# Power_Supply_Section.net
KiCad netlist of a schematic drawn in Altium Designer
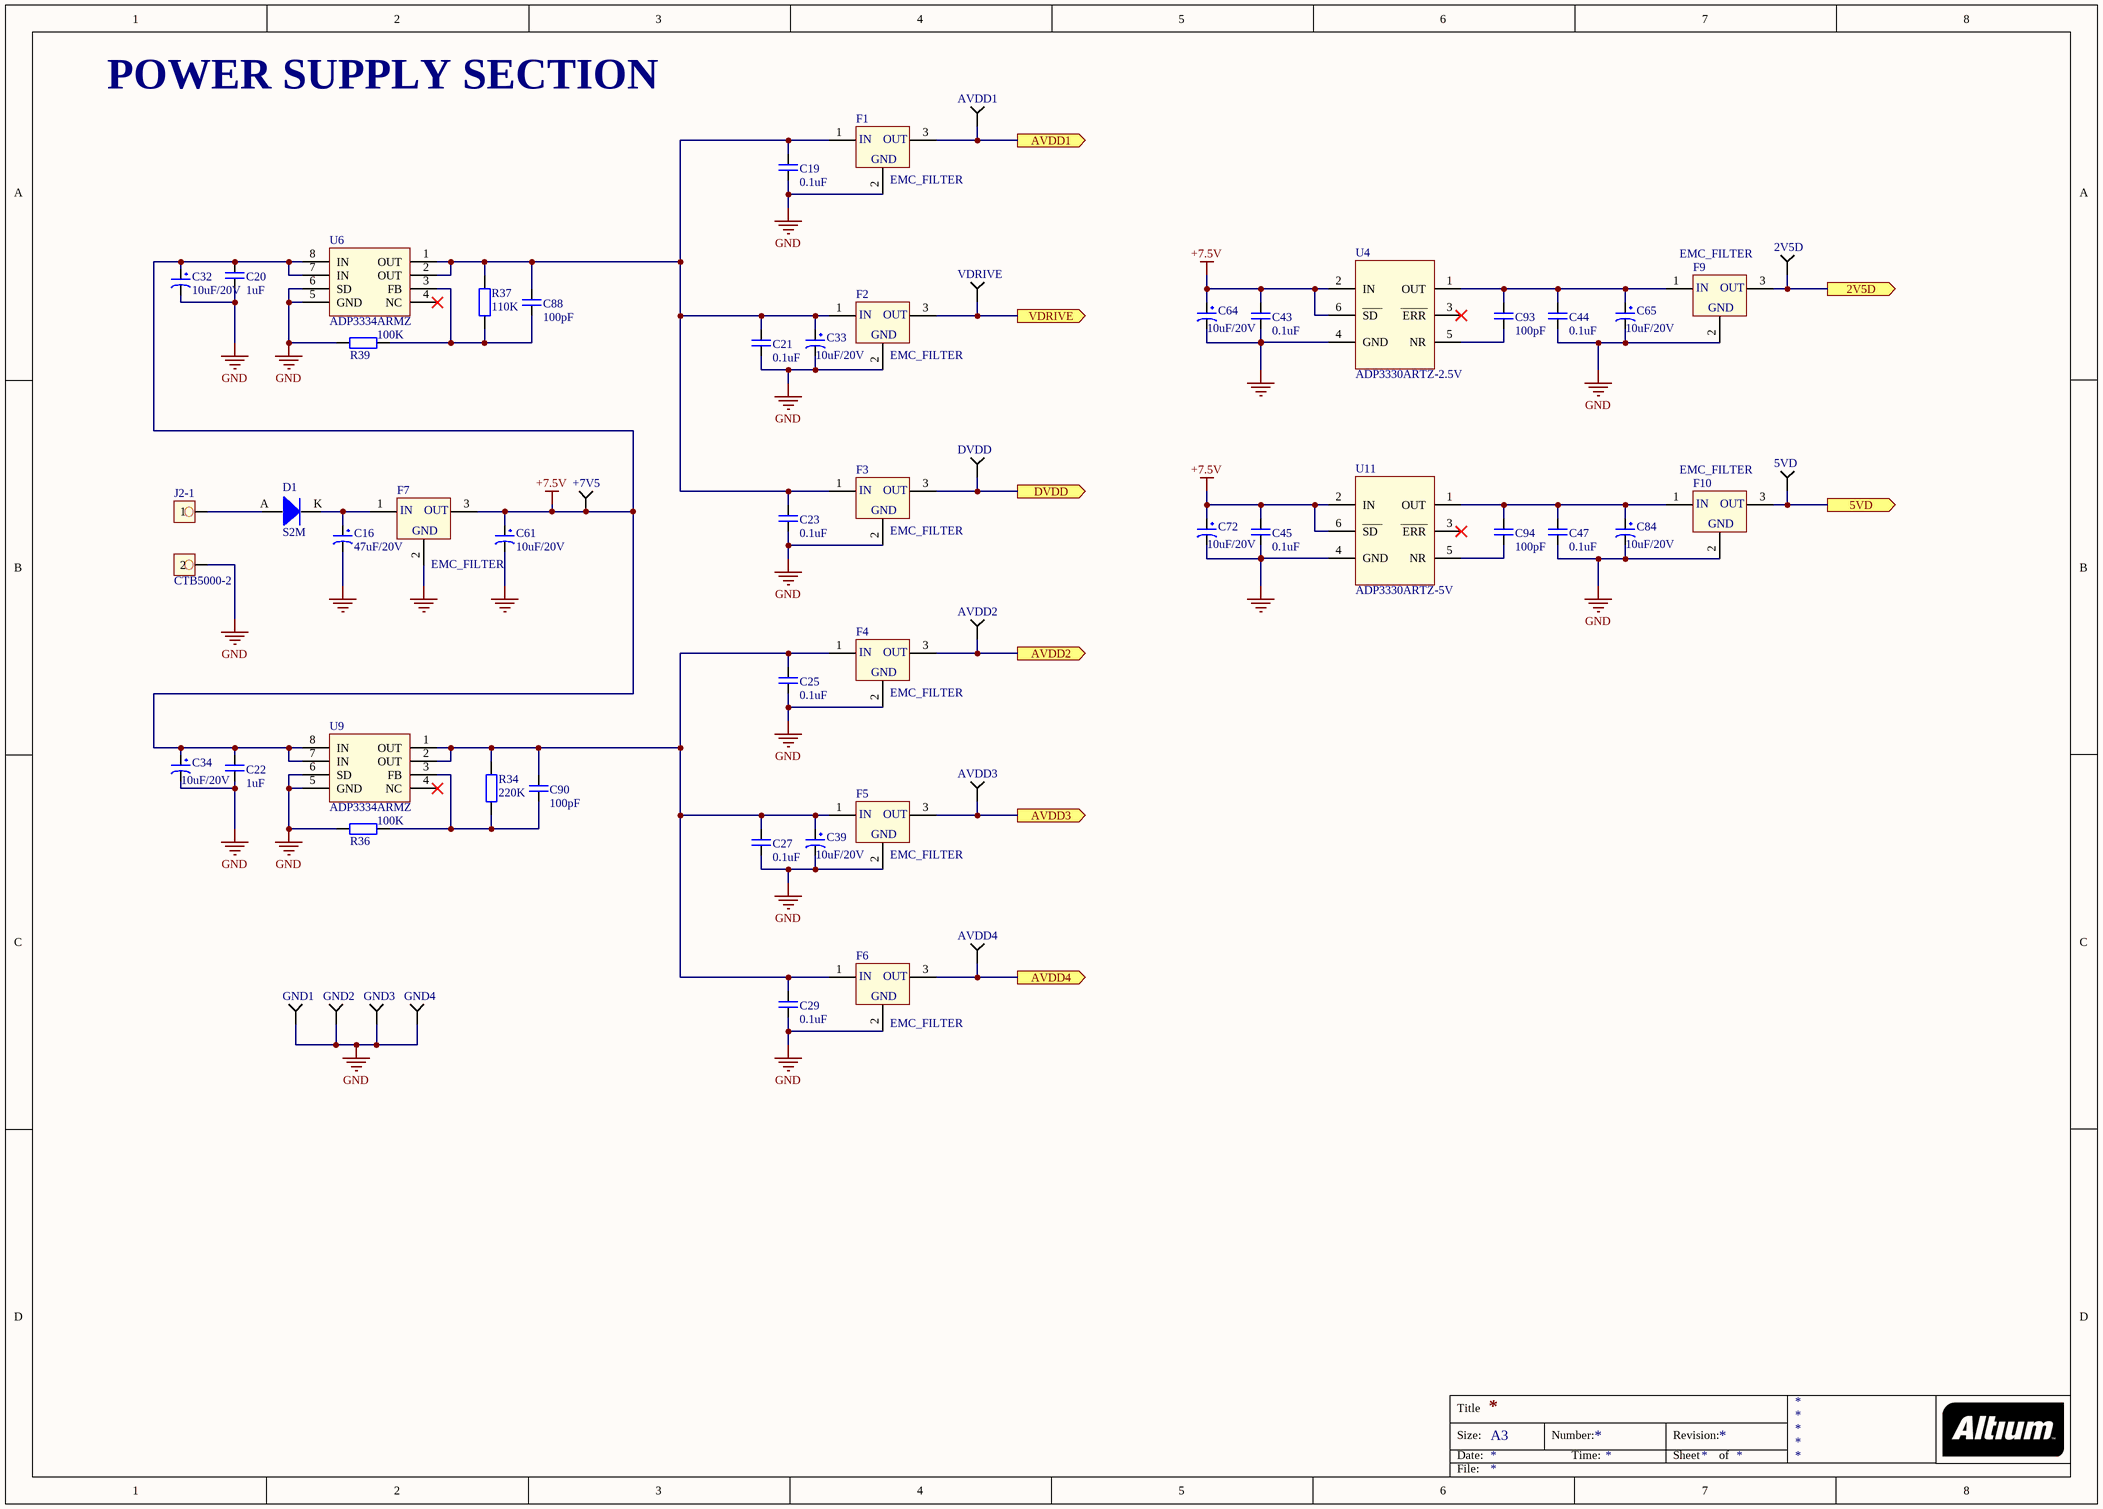
[diagram p0: Power Supply Section.SchDoc]

(export (version "E")
  (design (tool "Eeschema 10.0.6"))
  (components
    (comp (ref "+7V5")
      (value "Test point")
      (footprint "Test Point")
      (description "CONN HEADER VERT .100 1POS 30AU")
      (fields
        (field (name "MANUFACTURER") "TE Connectivity AMP Connectors")
        (field (name "MANUFACTURER PART NUMBER") "87220-1")
      )
      (libsource (lib "AD7763EDZ_Schematics Library") (part "Testpoint_PIN"))
    )
    (comp (ref "2V5D")
      (value "Test point")
      (footprint "Test Point")
      (description "CONN HEADER VERT .100 1POS 30AU")
      (fields
        (field (name "MANUFACTURER") "TE Connectivity AMP Connectors")
        (field (name "MANUFACTURER PART NUMBER") "87220-1")
      )
      (libsource (lib "AD7763EDZ_Schematics Library") (part "Testpoint_PIN"))
    )
    (comp (ref "5VD")
      (value "Test point")
      (footprint "Test Point")
      (description "CONN HEADER VERT .100 1POS 30AU")
      (fields
        (field (name "MANUFACTURER") "TE Connectivity AMP Connectors")
        (field (name "MANUFACTURER PART NUMBER") "87220-1")
      )
      (libsource (lib "AD7763EDZ_Schematics Library") (part "Testpoint_PIN"))
    )
    (comp (ref "AVDD1")
      (value "Test point")
      (footprint "Test Point")
      (description "CONN HEADER VERT .100 1POS 30AU")
      (fields
        (field (name "MANUFACTURER") "TE Connectivity AMP Connectors")
        (field (name "MANUFACTURER PART NUMBER") "87220-1")
      )
      (libsource (lib "AD7763EDZ_Schematics Library") (part "Testpoint_PIN"))
    )
    (comp (ref "AVDD2")
      (value "Test point")
      (footprint "Test Point")
      (description "CONN HEADER VERT .100 1POS 30AU")
      (fields
        (field (name "MANUFACTURER") "TE Connectivity AMP Connectors")
        (field (name "MANUFACTURER PART NUMBER") "87220-1")
      )
      (libsource (lib "AD7763EDZ_Schematics Library") (part "Testpoint_PIN"))
    )
    (comp (ref "AVDD3")
      (value "Test point")
      (footprint "Test Point")
      (description "CONN HEADER VERT .100 1POS 30AU")
      (fields
        (field (name "MANUFACTURER") "TE Connectivity AMP Connectors")
        (field (name "MANUFACTURER PART NUMBER") "87220-1")
      )
      (libsource (lib "AD7763EDZ_Schematics Library") (part "Testpoint_PIN"))
    )
    (comp (ref "AVDD4")
      (value "Test point")
      (footprint "Test Point")
      (description "CONN HEADER VERT .100 1POS 30AU")
      (fields
        (field (name "MANUFACTURER") "TE Connectivity AMP Connectors")
        (field (name "MANUFACTURER PART NUMBER") "87220-1")
      )
      (libsource (lib "AD7763EDZ_Schematics Library") (part "Testpoint_PIN"))
    )
    (comp (ref "C16")
      (value "47uF/20V")
      (footprint "C_TANTA_TAJ-D")
      (description "CAP TANT 47UF 20V 10% 2917_TAJ-D")
      (fields
        (field (name "MANUFACTURER") "AVX Corporation")
        (field (name "MANUFACTURER PART NUMBER") "TAJD476K020RNJ")
      )
      (libsource (lib "AD7763EDZ_Schematics Library") (part "C_TANTA_47uF_20V"))
    )
    (comp (ref "C19")
      (value "0.1uF")
      (footprint "C_0805")
      (description "CAP CER 0.1UF 50V 10% X7R 0805")
      (fields
        (field (name "MANUFACTURER") "MULTICOMP")
        (field (name "MANUFACTURER PART NUMBER") "MCU0805R104KCT")
      )
      (libsource (lib "AD7763EDZ_Schematics Library") (part "C_0.1uF_0805"))
    )
    (comp (ref "C20")
      (value "1uF")
      (footprint "C_0805")
      (description "CAP CER 1UF 16V 10% X7R 0805")
      (fields
        (field (name "MANUFACTURER") "Murata Electronics North America")
        (field (name "MANUFACTURER PART NUMBER") "GRM21BR71C105KA01L")
      )
      (libsource (lib "AD7763EDZ_Schematics Library") (part "C_1uF"))
    )
    (comp (ref "C21")
      (value "0.1uF")
      (footprint "C_0805")
      (description "CAP CER 0.1UF 50V 10% X7R 0805")
      (fields
        (field (name "MANUFACTURER") "MULTICOMP")
        (field (name "MANUFACTURER PART NUMBER") "MCU0805R104KCT")
      )
      (libsource (lib "AD7763EDZ_Schematics Library") (part "C_0.1uF_0805"))
    )
    (comp (ref "C22")
      (value "1uF")
      (footprint "C_0805")
      (description "CAP CER 1UF 16V 10% X7R 0805")
      (fields
        (field (name "MANUFACTURER") "Murata Electronics North America")
        (field (name "MANUFACTURER PART NUMBER") "GRM21BR71C105KA01L")
      )
      (libsource (lib "AD7763EDZ_Schematics Library") (part "C_1uF_0805"))
    )
    (comp (ref "C23")
      (value "0.1uF")
      (footprint "C_0805")
      (description "CAP CER 0.1UF 50V 10% X7R 0805")
      (fields
        (field (name "MANUFACTURER") "MULTICOMP")
        (field (name "MANUFACTURER PART NUMBER") "MCU0805R104KCT")
      )
      (libsource (lib "AD7763EDZ_Schematics Library") (part "C_0.1uF_0805"))
    )
    (comp (ref "C25")
      (value "0.1uF")
      (footprint "C_0805")
      (description "CAP CER 0.1UF 50V 10% X7R 0805")
      (fields
        (field (name "MANUFACTURER") "MULTICOMP")
        (field (name "MANUFACTURER PART NUMBER") "MCU0805R104KCT")
      )
      (libsource (lib "AD7763EDZ_Schematics Library") (part "C_0.1uF_0805"))
    )
    (comp (ref "C27")
      (value "0.1uF")
      (footprint "C_0805")
      (description "CAP CER 0.1UF 50V 10% X7R 0805")
      (fields
        (field (name "MANUFACTURER") "MULTICOMP")
        (field (name "MANUFACTURER PART NUMBER") "MCU0805R104KCT")
      )
      (libsource (lib "AD7763EDZ_Schematics Library") (part "C_0.1uF_0805"))
    )
    (comp (ref "C29")
      (value "0.1uF")
      (footprint "C_0805")
      (description "CAP CER 0.1UF 50V 10% X7R 0805")
      (fields
        (field (name "MANUFACTURER") "MULTICOMP")
        (field (name "MANUFACTURER PART NUMBER") "MCU0805R104KCT")
      )
      (libsource (lib "AD7763EDZ_Schematics Library") (part "C_0.1uF_0805"))
    )
    (comp (ref "C32")
      (value "10uF/20V")
      (footprint "C_TANTA_TAJ-B")
      (description "CAP TANT 10UF 20V 10% 1210")
      (fields
        (field (name "MANUFACTURER") "AVX Corporation")
        (field (name "MANUFACTURER PART NUMBER") "TAJB106K020RNJ")
      )
      (libsource (lib "AD7763EDZ_Schematics Library") (part "C_TANTA_10uF_20V"))
    )
    (comp (ref "C33")
      (value "10uF/20V")
      (footprint "C_TANTA_TAJ-B")
      (description "CAP TANT 10UF 20V 10% 1210")
      (fields
        (field (name "MANUFACTURER") "AVX Corporation")
        (field (name "MANUFACTURER PART NUMBER") "TAJB106K020RNJ")
      )
      (libsource (lib "AD7763EDZ_Schematics Library") (part "C_TANTA_10uF_20V"))
    )
    (comp (ref "C34")
      (value "10uF/20V")
      (footprint "C_TANTA_TAJ-B")
      (description "CAP TANT 10UF 20V 10% 1210")
      (fields
        (field (name "MANUFACTURER") "AVX Corporation")
        (field (name "MANUFACTURER PART NUMBER") "TAJB106K020RNJ")
      )
      (libsource (lib "AD7763EDZ_Schematics Library") (part "C_TANTA_10uF_20V"))
    )
    (comp (ref "C39")
      (value "10uF/20V")
      (footprint "C_TANTA_TAJ-B")
      (description "CAP TANT 10UF 20V 10% 1210")
      (fields
        (field (name "MANUFACTURER") "AVX Corporation")
        (field (name "MANUFACTURER PART NUMBER") "TAJB106K020RNJ")
      )
      (libsource (lib "AD7763EDZ_Schematics Library") (part "C_TANTA_10uF_20V"))
    )
    (comp (ref "C43")
      (value "0.1uF")
      (footprint "C_0805")
      (description "CAP CER 0.1UF 50V 10% X7R 0805")
      (fields
        (field (name "MANUFACTURER") "MULTICOMP")
        (field (name "MANUFACTURER PART NUMBER") "MCU0805R104KCT")
      )
      (libsource (lib "AD7763EDZ_Schematics Library") (part "C_0.1uF_0805"))
    )
    (comp (ref "C44")
      (value "0.1uF")
      (footprint "C_0805")
      (description "CAP CER 0.1UF 50V 10% X7R 0805")
      (fields
        (field (name "MANUFACTURER") "MULTICOMP")
        (field (name "MANUFACTURER PART NUMBER") "MCU0805R104KCT")
      )
      (libsource (lib "AD7763EDZ_Schematics Library") (part "C_0.1uF_0805"))
    )
    (comp (ref "C45")
      (value "0.1uF")
      (footprint "C_0805")
      (description "CAP CER 0.1UF 50V 10% X7R 0805")
      (fields
        (field (name "MANUFACTURER") "MULTICOMP")
        (field (name "MANUFACTURER PART NUMBER") "MCU0805R104KCT")
      )
      (libsource (lib "AD7763EDZ_Schematics Library") (part "C_0.1uF_0805"))
    )
    (comp (ref "C47")
      (value "0.1uF")
      (footprint "C_0805")
      (description "CAP CER 0.1UF 50V 10% X7R 0805")
      (fields
        (field (name "MANUFACTURER") "MULTICOMP")
        (field (name "MANUFACTURER PART NUMBER") "MCU0805R104KCT")
      )
      (libsource (lib "AD7763EDZ_Schematics Library") (part "C_0.1uF_0805"))
    )
    (comp (ref "C61")
      (value "10uF/20V")
      (footprint "C_TANTA_TAJ-B")
      (description "CAP TANT 10UF 20V 10% 1210")
      (fields
        (field (name "MANUFACTURER") "AVX Corporation")
        (field (name "MANUFACTURER PART NUMBER") "TAJB106K020RNJ")
      )
      (libsource (lib "AD7763EDZ_Schematics Library") (part "C_TANTA_10uF_20V"))
    )
    (comp (ref "C64")
      (value "10uF/20V")
      (footprint "C_TANTA_TAJ-B")
      (description "CAP TANT 10UF 20V 10% 1210")
      (fields
        (field (name "MANUFACTURER") "AVX Corporation")
        (field (name "MANUFACTURER PART NUMBER") "TAJB106K020RNJ")
      )
      (libsource (lib "AD7763EDZ_Schematics Library") (part "C_TANTA_10uF_20V"))
    )
    (comp (ref "C65")
      (value "10uF/20V")
      (footprint "C_TANTA_TAJ-B")
      (description "CAP TANT 10UF 20V 10% 1210")
      (fields
        (field (name "MANUFACTURER") "AVX Corporation")
        (field (name "MANUFACTURER PART NUMBER") "TAJB106K020RNJ")
      )
      (libsource (lib "AD7763EDZ_Schematics Library") (part "C_TANTA_10uF_20V"))
    )
    (comp (ref "C72")
      (value "10uF/20V")
      (footprint "C_TANTA_TAJ-B")
      (description "CAP TANT 10UF 20V 10% 1210")
      (fields
        (field (name "MANUFACTURER") "AVX Corporation")
        (field (name "MANUFACTURER PART NUMBER") "TAJB106K020RNJ")
      )
      (libsource (lib "AD7763EDZ_Schematics Library") (part "C_TANTA_10uF_20V"))
    )
    (comp (ref "C84")
      (value "10uF/20V")
      (footprint "C_TANTA_TAJ-B")
      (description "CAP TANT 10UF 20V 10% 1210")
      (fields
        (field (name "MANUFACTURER") "AVX Corporation")
        (field (name "MANUFACTURER PART NUMBER") "TAJB106K020RNJ")
      )
      (libsource (lib "AD7763EDZ_Schematics Library") (part "C_TANTA_10uF_20V"))
    )
    (comp (ref "C88")
      (value "100pF")
      (footprint "C0603")
      (description "CAP CER 100PF 50V 5% NP0 0603")
      (fields
        (field (name "MANUFACTURER") "MULTICOMP")
        (field (name "MANUFACTURER PART NUMBER") "MCU0603C101JCT")
      )
      (libsource (lib "AD7763EDZ_Schematics Library") (part "C_100pF_0603"))
    )
    (comp (ref "C90")
      (value "100pF")
      (footprint "C0603")
      (description "CAP CER 100PF 50V 5% NP0 0603")
      (fields
        (field (name "MANUFACTURER") "MULTICOMP")
        (field (name "MANUFACTURER PART NUMBER") "MCU0603C101JCT")
      )
      (libsource (lib "AD7763EDZ_Schematics Library") (part "C_100pF_0603"))
    )
    (comp (ref "C93")
      (value "100pF")
      (footprint "C0603")
      (description "CAP CER 100PF 50V 5% NP0 0603")
      (fields
        (field (name "MANUFACTURER") "MULTICOMP")
        (field (name "MANUFACTURER PART NUMBER") "MCU0603C101JCT")
      )
      (libsource (lib "AD7763EDZ_Schematics Library") (part "C_100pF_0603"))
    )
    (comp (ref "C94")
      (value "100pF")
      (footprint "C0603")
      (description "CAP CER 100PF 50V 5% NP0 0603")
      (fields
        (field (name "MANUFACTURER") "MULTICOMP")
        (field (name "MANUFACTURER PART NUMBER") "MCU0603C101JCT")
      )
      (libsource (lib "AD7763EDZ_Schematics Library") (part "C_100pF_0603"))
    )
    (comp (ref "D1")
      (value "S2M")
      (footprint "SS14_AK")
      (description "DIODE GEN PURP 1KV 2A DO214AA")
      (fields (field (name "MANUFACTURER") "Fairchild Semiconductor"))
      (libsource (lib "AD7763EDZ_Schematics Library") (part "D_S2M"))
    )
    (comp (ref "DVDD")
      (value "Test point")
      (footprint "Test Point")
      (description "CONN HEADER VERT .100 1POS 30AU")
      (fields
        (field (name "MANUFACTURER") "TE Connectivity AMP Connectors")
        (field (name "MANUFACTURER PART NUMBER") "87220-1")
      )
      (libsource (lib "AD7763EDZ_Schematics Library") (part "Testpoint_PIN"))
    )
    (comp (ref "F1")
      (value "EMC_FILTER")
      (footprint "EMC_FILTER")
      (description "FILTER LC HIGH FREQ 1000PF 2606")
      (fields
        (field (name "MANUFACTURER") "Murata Electronics North America")
        (field (name "MANUFACTURER PART NUMBER") "NFE61PT102E1H9L")
      )
      (libsource (lib "AD7763EDZ_Schematics Library") (part "EMC_FILTER"))
    )
    (comp (ref "F2")
      (value "EMC_FILTER")
      (footprint "EMC_FILTER")
      (description "FILTER LC HIGH FREQ 1000PF 2606")
      (fields
        (field (name "MANUFACTURER") "Murata Electronics North America")
        (field (name "MANUFACTURER PART NUMBER") "NFE61PT102E1H9L")
      )
      (libsource (lib "AD7763EDZ_Schematics Library") (part "EMC_FILTER"))
    )
    (comp (ref "F3")
      (value "EMC_FILTER")
      (footprint "EMC_FILTER")
      (description "FILTER LC HIGH FREQ 1000PF 2606")
      (fields
        (field (name "MANUFACTURER") "Murata Electronics North America")
        (field (name "MANUFACTURER PART NUMBER") "NFE61PT102E1H9L")
      )
      (libsource (lib "AD7763EDZ_Schematics Library") (part "EMC_FILTER"))
    )
    (comp (ref "F4")
      (value "EMC_FILTER")
      (footprint "EMC_FILTER")
      (description "FILTER LC HIGH FREQ 1000PF 2606")
      (fields
        (field (name "MANUFACTURER") "Murata Electronics North America")
        (field (name "MANUFACTURER PART NUMBER") "NFE61PT102E1H9L")
      )
      (libsource (lib "AD7763EDZ_Schematics Library") (part "EMC_FILTER"))
    )
    (comp (ref "F5")
      (value "EMC_FILTER")
      (footprint "EMC_FILTER")
      (description "FILTER LC HIGH FREQ 1000PF 2606")
      (fields
        (field (name "MANUFACTURER") "Murata Electronics North America")
        (field (name "MANUFACTURER PART NUMBER") "NFE61PT102E1H9L")
      )
      (libsource (lib "AD7763EDZ_Schematics Library") (part "EMC_FILTER"))
    )
    (comp (ref "F6")
      (value "EMC_FILTER")
      (footprint "EMC_FILTER")
      (description "FILTER LC HIGH FREQ 1000PF 2606")
      (fields
        (field (name "MANUFACTURER") "Murata Electronics North America")
        (field (name "MANUFACTURER PART NUMBER") "NFE61PT102E1H9L")
      )
      (libsource (lib "AD7763EDZ_Schematics Library") (part "EMC_FILTER"))
    )
    (comp (ref "F7")
      (value "EMC_FILTER")
      (footprint "EMC_FILTER")
      (description "FILTER LC HIGH FREQ 1000PF 2606")
      (fields
        (field (name "MANUFACTURER") "Murata Electronics North America")
        (field (name "MANUFACTURER PART NUMBER") "NFE61PT102E1H9L")
      )
      (libsource (lib "AD7763EDZ_Schematics Library") (part "EMC_FILTER"))
    )
    (comp (ref "F9")
      (value "EMC_FILTER")
      (footprint "EMC_FILTER")
      (description "FILTER LC HIGH FREQ 1000PF 2606")
      (fields
        (field (name "MANUFACTURER") "Murata Electronics North America")
        (field (name "MANUFACTURER PART NUMBER") "NFE61PT102E1H9L")
      )
      (libsource (lib "AD7763EDZ_Schematics Library") (part "EMC_FILTER"))
    )
    (comp (ref "F10")
      (value "EMC_FILTER")
      (footprint "EMC_FILTER")
      (description "FILTER LC HIGH FREQ 1000PF 2606")
      (fields
        (field (name "MANUFACTURER") "Murata Electronics North America")
        (field (name "MANUFACTURER PART NUMBER") "NFE61PT102E1H9L")
      )
      (libsource (lib "AD7763EDZ_Schematics Library") (part "EMC_FILTER"))
    )
    (comp (ref "GND1")
      (value "Test point")
      (footprint "Test Point")
      (description "CONN HEADER VERT .100 1POS 30AU")
      (fields
        (field (name "MANUFACTURER") "TE Connectivity AMP Connectors")
        (field (name "MANUFACTURER PART NUMBER") "87220-1")
      )
      (libsource (lib "AD7763EDZ_Schematics Library") (part "Testpoint_PIN"))
    )
    (comp (ref "GND2")
      (value "Test point")
      (footprint "Test Point")
      (description "CONN HEADER VERT .100 1POS 30AU")
      (fields
        (field (name "MANUFACTURER") "TE Connectivity AMP Connectors")
        (field (name "MANUFACTURER PART NUMBER") "87220-1")
      )
      (libsource (lib "AD7763EDZ_Schematics Library") (part "Testpoint_PIN"))
    )
    (comp (ref "GND3")
      (value "Test point")
      (footprint "Test Point")
      (description "CONN HEADER VERT .100 1POS 30AU")
      (fields
        (field (name "MANUFACTURER") "TE Connectivity AMP Connectors")
        (field (name "MANUFACTURER PART NUMBER") "87220-1")
      )
      (libsource (lib "AD7763EDZ_Schematics Library") (part "Testpoint_PIN"))
    )
    (comp (ref "GND4")
      (value "Test point")
      (footprint "Test Point")
      (description "CONN HEADER VERT .100 1POS 30AU")
      (fields
        (field (name "MANUFACTURER") "TE Connectivity AMP Connectors")
        (field (name "MANUFACTURER PART NUMBER") "87220-1")
      )
      (libsource (lib "AD7763EDZ_Schematics Library") (part "Testpoint_PIN"))
    )
    (comp (ref "J2-1")
      (value "CTB5000-2")
      (footprint "CTB5000-2")
      (description "TERMINAL BLOCK, WIRE TO BRD, 2POS, 14AWG")
      (fields
        (field (name "MANUFACTURER") "CAMDENBOSS")
        (field (name "MANUFACTURER PART NUMBER") "CTB5000/2")
      )
      (libsource (lib "AD7763EDZ_Schematics Library") (part "HEADER_2"))
    )
    (comp (ref "R34")
      (value "220K")
      (footprint "R_0603")
      (description "RES SMD 220K OHM 1% 1/16W 0603")
      (fields
        (field (name "MANUFACTURER") "MULTICOMP")
        (field (name "MANUFACTURER PART NUMBER") "MC0063W06031220K")
      )
      (libsource (lib "AD7763EDZ_Schematics Library") (part "R_0603_220K"))
    )
    (comp (ref "R36")
      (value "100K")
      (footprint "R_0603")
      (description "RES SMD 100K OHM 1% 1/16W 0603")
      (fields
        (field (name "MANUFACTURER") "MULTICOMP")
        (field (name "MANUFACTURER PART NUMBER") "MC0063W06031100K")
      )
      (libsource (lib "AD7763EDZ_Schematics Library") (part "R_0603_100K"))
    )
    (comp (ref "R37")
      (value "110K")
      (footprint "R_0603")
      (description "RES SMD 110K OHM 1% 1/16W 0603")
      (fields
        (field (name "MANUFACTURER") "MULTICOMP")
        (field (name "MANUFACTURER PART NUMBER") "MC0063W06031110K")
      )
      (libsource (lib "AD7763EDZ_Schematics Library") (part "R_0603_110K"))
    )
    (comp (ref "R39")
      (value "100K")
      (footprint "R_0603")
      (description "RES SMD 100K OHM 1% 1/16W 0603")
      (fields
        (field (name "MANUFACTURER") "MULTICOMP")
        (field (name "MANUFACTURER PART NUMBER") "MC0063W06031100K")
      )
      (libsource (lib "AD7763EDZ_Schematics Library") (part "R_0603_100K"))
    )
    (comp (ref "U4")
      (value "ADP3330ARTZ-2.5V")
      (footprint "SOT-23-6")
      (description "IC REG LDO 2.5V 0.2A SOT23-6")
      (fields
        (field (name "MANUFACTURER") "Analog Devices Inc.")
        (field (name "MANUFACTURER PART NUMBER") "ADP3330ARTZ-2.5-R7")
      )
      (libsource (lib "AD7763EDZ_Schematics Library") (part "ADP3330ARTZ-2.5V"))
    )
    (comp (ref "U6")
      (value "ADP3334ARMZ")
      (footprint "MSOP-8")
      (description "IC REG LDO ADJ 0.5A 8MSOP")
      (fields
        (field (name "MANUFACTURER") "Analog Devices Inc")
        (field (name "MANUFACTURER PART NUMBER") "ADP3334ARMZ-REEL")
      )
      (libsource (lib "AD7763EDZ_Schematics Library") (part "ADP3334ARMZ"))
    )
    (comp (ref "U9")
      (value "ADP3334ARMZ")
      (footprint "MSOP-8")
      (description "IC REG LDO ADJ 0.5A 8MSOP")
      (fields
        (field (name "MANUFACTURER") "Analog Devices Inc")
        (field (name "MANUFACTURER PART NUMBER") "ADP3334ARMZ-REEL")
      )
      (libsource (lib "AD7763EDZ_Schematics Library") (part "ADP3334ARMZ"))
    )
    (comp (ref "U11")
      (value "ADP3330ARTZ-5V")
      (footprint "SOT-23-6")
      (description "IC REG LDO 5V 0.2A SOT23-6")
      (fields
        (field (name "MANUFACTURER") "Analog Devices Inc.")
        (field (name "MANUFACTURER PART NUMBER") "ADP3330ARTZ-5-RL7")
      )
      (libsource (lib "AD7763EDZ_Schematics Library") (part "ADP3330ARTZ-5V"))
    )
    (comp (ref "VDRIVE")
      (value "Test point")
      (footprint "Test Point")
      (description "CONN HEADER VERT .100 1POS 30AU")
      (fields
        (field (name "MANUFACTURER") "TE Connectivity AMP Connectors")
        (field (name "MANUFACTURER PART NUMBER") "87220-1")
      )
      (libsource (lib "AD7763EDZ_Schematics Library") (part "Testpoint_PIN"))
    )
  )
  (nets
    (net (code "1") (name "+7.5V") (class "Default")
      (node (ref "+7V5") (pin "1") (pinfunction "1_1") (pintype "passive"))
      (node (ref "C20") (pin "1") (pinfunction "1_1") (pintype "passive"))
      (node (ref "C22") (pin "1") (pinfunction "1_1") (pintype "passive"))
      (node (ref "C32") (pin "1") (pinfunction "1_1") (pintype "passive"))
      (node (ref "C34") (pin "1") (pinfunction "1_1") (pintype "passive"))
      (node (ref "C43") (pin "1") (pinfunction "1_1") (pintype "passive"))
      (node (ref "C45") (pin "1") (pinfunction "1_1") (pintype "passive"))
      (node (ref "C61") (pin "1") (pinfunction "1_1") (pintype "passive"))
      (node (ref "C64") (pin "1") (pinfunction "1_1") (pintype "passive"))
      (node (ref "C72") (pin "1") (pinfunction "1_1") (pintype "passive"))
      (node (ref "F7") (pin "3") (pinfunction "OUT_3") (pintype "passive"))
      (node (ref "U11") (pin "2") (pinfunction "IN_2") (pintype "passive"))
      (node (ref "U11") (pin "6") (pinfunction "SD_6") (pintype "passive"))
      (node (ref "U4") (pin "2") (pinfunction "IN_2") (pintype "passive"))
      (node (ref "U4") (pin "6") (pinfunction "SD_6") (pintype "passive"))
      (node (ref "U6") (pin "7") (pinfunction "IN_7") (pintype "passive"))
      (node (ref "U6") (pin "8") (pinfunction "IN_8") (pintype "passive"))
      (node (ref "U9") (pin "7") (pinfunction "IN_7") (pintype "passive"))
      (node (ref "U9") (pin "8") (pinfunction "IN_8") (pintype "passive"))
    )
    (net (code "2") (name "/2V5D") (class "Default")
      (node (ref "2V5D") (pin "1") (pinfunction "1_1") (pintype "passive"))
      (node (ref "F9") (pin "3") (pinfunction "OUT_3") (pintype "passive"))
    )
    (net (code "3") (name "/5VD") (class "Default")
      (node (ref "5VD") (pin "1") (pinfunction "1_1") (pintype "passive"))
      (node (ref "F10") (pin "3") (pinfunction "OUT_3") (pintype "passive"))
    )
    (net (code "4") (name "/AVDD1") (class "Default")
      (node (ref "AVDD1") (pin "1") (pinfunction "1_1") (pintype "passive"))
      (node (ref "F1") (pin "3") (pinfunction "OUT_3") (pintype "passive"))
    )
    (net (code "5") (name "/AVDD2") (class "Default")
      (node (ref "AVDD2") (pin "1") (pinfunction "1_1") (pintype "passive"))
      (node (ref "F4") (pin "3") (pinfunction "OUT_3") (pintype "passive"))
    )
    (net (code "6") (name "/AVDD3") (class "Default")
      (node (ref "AVDD3") (pin "1") (pinfunction "1_1") (pintype "passive"))
      (node (ref "F5") (pin "3") (pinfunction "OUT_3") (pintype "passive"))
    )
    (net (code "7") (name "/AVDD4") (class "Default")
      (node (ref "AVDD4") (pin "1") (pinfunction "1_1") (pintype "passive"))
      (node (ref "F6") (pin "3") (pinfunction "OUT_3") (pintype "passive"))
    )
    (net (code "8") (name "/DVDD") (class "Default")
      (node (ref "DVDD") (pin "1") (pinfunction "1_1") (pintype "passive"))
      (node (ref "F3") (pin "3") (pinfunction "OUT_3") (pintype "passive"))
    )
    (net (code "9") (name "/VDRIVE") (class "Default")
      (node (ref "F2") (pin "3") (pinfunction "OUT_3") (pintype "passive"))
      (node (ref "VDRIVE") (pin "1") (pinfunction "1_1") (pintype "passive"))
    )
    (net (code "10") (name "<NO NET>") (class "Default")
      (node (ref "C16") (pin "2") (pinfunction "2_2") (pintype "passive"))
      (node (ref "C43") (pin "2") (pinfunction "2_2") (pintype "passive"))
      (node (ref "C45") (pin "2") (pinfunction "2_2") (pintype "passive"))
      (node (ref "C61") (pin "2") (pinfunction "2_2") (pintype "passive"))
      (node (ref "C64") (pin "2") (pinfunction "2_2") (pintype "passive"))
      (node (ref "C72") (pin "2") (pinfunction "2_2") (pintype "passive"))
      (node (ref "F7") (pin "2") (pinfunction "GND_2") (pintype "passive"))
      (node (ref "U11") (pin "4") (pinfunction "GND_4") (pintype "passive"))
      (node (ref "U4") (pin "4") (pinfunction "GND_4") (pintype "passive"))
    )
    (net (code "11") (name "GND") (class "Default")
      (node (ref "C19") (pin "2") (pinfunction "2_2") (pintype "passive"))
      (node (ref "C20") (pin "2") (pinfunction "2_2") (pintype "passive"))
      (node (ref "C21") (pin "2") (pinfunction "2_2") (pintype "passive"))
      (node (ref "C22") (pin "2") (pinfunction "2_2") (pintype "passive"))
      (node (ref "C23") (pin "2") (pinfunction "2_2") (pintype "passive"))
      (node (ref "C25") (pin "2") (pinfunction "2_2") (pintype "passive"))
      (node (ref "C27") (pin "2") (pinfunction "2_2") (pintype "passive"))
      (node (ref "C29") (pin "2") (pinfunction "2_2") (pintype "passive"))
      (node (ref "C32") (pin "2") (pinfunction "2_2") (pintype "passive"))
      (node (ref "C33") (pin "2") (pinfunction "2_2") (pintype "passive"))
      (node (ref "C34") (pin "2") (pinfunction "2_2") (pintype "passive"))
      (node (ref "C39") (pin "2") (pinfunction "2_2") (pintype "passive"))
      (node (ref "C44") (pin "2") (pinfunction "2_2") (pintype "passive"))
      (node (ref "C47") (pin "2") (pinfunction "2_2") (pintype "passive"))
      (node (ref "C65") (pin "2") (pinfunction "2_2") (pintype "passive"))
      (node (ref "C84") (pin "2") (pinfunction "2_2") (pintype "passive"))
      (node (ref "F1") (pin "2") (pinfunction "GND_2") (pintype "passive"))
      (node (ref "F10") (pin "2") (pinfunction "GND_2") (pintype "passive"))
      (node (ref "F2") (pin "2") (pinfunction "GND_2") (pintype "passive"))
      (node (ref "F3") (pin "2") (pinfunction "GND_2") (pintype "passive"))
      (node (ref "F4") (pin "2") (pinfunction "GND_2") (pintype "passive"))
      (node (ref "F5") (pin "2") (pinfunction "GND_2") (pintype "passive"))
      (node (ref "F6") (pin "2") (pinfunction "GND_2") (pintype "passive"))
      (node (ref "F9") (pin "2") (pinfunction "GND_2") (pintype "passive"))
      (node (ref "GND1") (pin "1") (pinfunction "1_1") (pintype "passive"))
      (node (ref "GND2") (pin "1") (pinfunction "1_1") (pintype "passive"))
      (node (ref "GND3") (pin "1") (pinfunction "1_1") (pintype "passive"))
      (node (ref "GND4") (pin "1") (pinfunction "1_1") (pintype "passive"))
      (node (ref "J2-1") (pin "2") (pinfunction "2_2") (pintype "passive"))
      (node (ref "R36") (pin "1") (pinfunction "1_1") (pintype "passive"))
      (node (ref "R39") (pin "1") (pinfunction "1_1") (pintype "passive"))
      (node (ref "U6") (pin "5") (pinfunction "GND_5") (pintype "passive"))
      (node (ref "U6") (pin "6") (pinfunction "SD_6") (pintype "passive"))
      (node (ref "U9") (pin "5") (pinfunction "GND_5") (pintype "passive"))
      (node (ref "U9") (pin "6") (pinfunction "SD_6") (pintype "passive"))
    )
    (net (code "12") (name "Net-(D1-PadA)") (class "Default")
      (node (ref "D1") (pin "A") (pinfunction "A_A") (pintype "passive"))
      (node (ref "J2-1") (pin "1") (pinfunction "1_1") (pintype "passive"))
    )
    (net (code "13") (name "Net-(F1-IN)") (class "Default")
      (node (ref "C19") (pin "1") (pinfunction "1_1") (pintype "passive"))
      (node (ref "C21") (pin "1") (pinfunction "1_1") (pintype "passive"))
      (node (ref "C23") (pin "1") (pinfunction "1_1") (pintype "passive"))
      (node (ref "C33") (pin "1") (pinfunction "1_1") (pintype "passive"))
      (node (ref "C88") (pin "1") (pinfunction "1_1") (pintype "passive"))
      (node (ref "F1") (pin "1") (pinfunction "IN_1") (pintype "passive"))
      (node (ref "F2") (pin "1") (pinfunction "IN_1") (pintype "passive"))
      (node (ref "F3") (pin "1") (pinfunction "IN_1") (pintype "passive"))
      (node (ref "R37") (pin "2") (pinfunction "2_2") (pintype "passive"))
      (node (ref "U6") (pin "1") (pinfunction "OUT_1") (pintype "passive"))
      (node (ref "U6") (pin "2") (pinfunction "OUT_2") (pintype "passive"))
    )
    (net (code "14") (name "Net-(F4-IN)") (class "Default")
      (node (ref "C25") (pin "1") (pinfunction "1_1") (pintype "passive"))
      (node (ref "C27") (pin "1") (pinfunction "1_1") (pintype "passive"))
      (node (ref "C29") (pin "1") (pinfunction "1_1") (pintype "passive"))
      (node (ref "C39") (pin "1") (pinfunction "1_1") (pintype "passive"))
      (node (ref "C90") (pin "1") (pinfunction "1_1") (pintype "passive"))
      (node (ref "F4") (pin "1") (pinfunction "IN_1") (pintype "passive"))
      (node (ref "F5") (pin "1") (pinfunction "IN_1") (pintype "passive"))
      (node (ref "F6") (pin "1") (pinfunction "IN_1") (pintype "passive"))
      (node (ref "R34") (pin "2") (pinfunction "2_2") (pintype "passive"))
      (node (ref "U9") (pin "1") (pinfunction "OUT_1") (pintype "passive"))
      (node (ref "U9") (pin "2") (pinfunction "OUT_2") (pintype "passive"))
    )
    (net (code "15") (name "Net-(F7-IN)") (class "Default")
      (node (ref "C16") (pin "1") (pinfunction "1_1") (pintype "passive"))
      (node (ref "D1") (pin "K") (pinfunction "K_K") (pintype "passive"))
      (node (ref "F7") (pin "1") (pinfunction "IN_1") (pintype "passive"))
    )
    (net (code "16") (name "Net-(F9-IN)") (class "Default")
      (node (ref "C44") (pin "1") (pinfunction "1_1") (pintype "passive"))
      (node (ref "C65") (pin "1") (pinfunction "1_1") (pintype "passive"))
      (node (ref "C93") (pin "1") (pinfunction "1_1") (pintype "passive"))
      (node (ref "F9") (pin "1") (pinfunction "IN_1") (pintype "passive"))
      (node (ref "U4") (pin "1") (pinfunction "OUT_1") (pintype "passive"))
    )
    (net (code "17") (name "Net-(F10-IN)") (class "Default")
      (node (ref "C47") (pin "1") (pinfunction "1_1") (pintype "passive"))
      (node (ref "C84") (pin "1") (pinfunction "1_1") (pintype "passive"))
      (node (ref "C94") (pin "1") (pinfunction "1_1") (pintype "passive"))
      (node (ref "F10") (pin "1") (pinfunction "IN_1") (pintype "passive"))
      (node (ref "U11") (pin "1") (pinfunction "OUT_1") (pintype "passive"))
    )
    (net (code "18") (name "Net-(U4-NR)") (class "Default")
      (node (ref "C93") (pin "2") (pinfunction "2_2") (pintype "passive"))
      (node (ref "U4") (pin "5") (pinfunction "NR_5") (pintype "passive"))
    )
    (net (code "19") (name "Net-(U6-FB)") (class "Default")
      (node (ref "C88") (pin "2") (pinfunction "2_2") (pintype "passive"))
      (node (ref "R37") (pin "1") (pinfunction "1_1") (pintype "passive"))
      (node (ref "R39") (pin "2") (pinfunction "2_2") (pintype "passive"))
      (node (ref "U6") (pin "3") (pinfunction "FB_3") (pintype "passive"))
    )
    (net (code "20") (name "Net-(U9-FB)") (class "Default")
      (node (ref "C90") (pin "2") (pinfunction "2_2") (pintype "passive"))
      (node (ref "R34") (pin "1") (pinfunction "1_1") (pintype "passive"))
      (node (ref "R36") (pin "2") (pinfunction "2_2") (pintype "passive"))
      (node (ref "U9") (pin "3") (pinfunction "FB_3") (pintype "passive"))
    )
    (net (code "21") (name "Net-(U11-NR)") (class "Default")
      (node (ref "C94") (pin "2") (pinfunction "2_2") (pintype "passive"))
      (node (ref "U11") (pin "5") (pinfunction "NR_5") (pintype "passive"))
    )
    (net (code "22") (name "unconnected-(U4-ERR-Pad3)") (class "Default")
      (node (ref "U4") (pin "3") (pinfunction "ERR_3") (pintype "passive+no_connect"))
    )
    (net (code "23") (name "unconnected-(U6-NC-Pad4)") (class "Default")
      (node (ref "U6") (pin "4") (pinfunction "NC_4") (pintype "passive+no_connect"))
    )
    (net (code "24") (name "unconnected-(U9-NC-Pad4)") (class "Default")
      (node (ref "U9") (pin "4") (pinfunction "NC_4") (pintype "passive+no_connect"))
    )
    (net (code "25") (name "unconnected-(U11-ERR-Pad3)") (class "Default")
      (node (ref "U11") (pin "3") (pinfunction "ERR_3") (pintype "passive+no_connect"))
    )
  )
)
